# 1-Schematic_starcard.net
KiCad netlist of a schematic drawn in EasyEDA
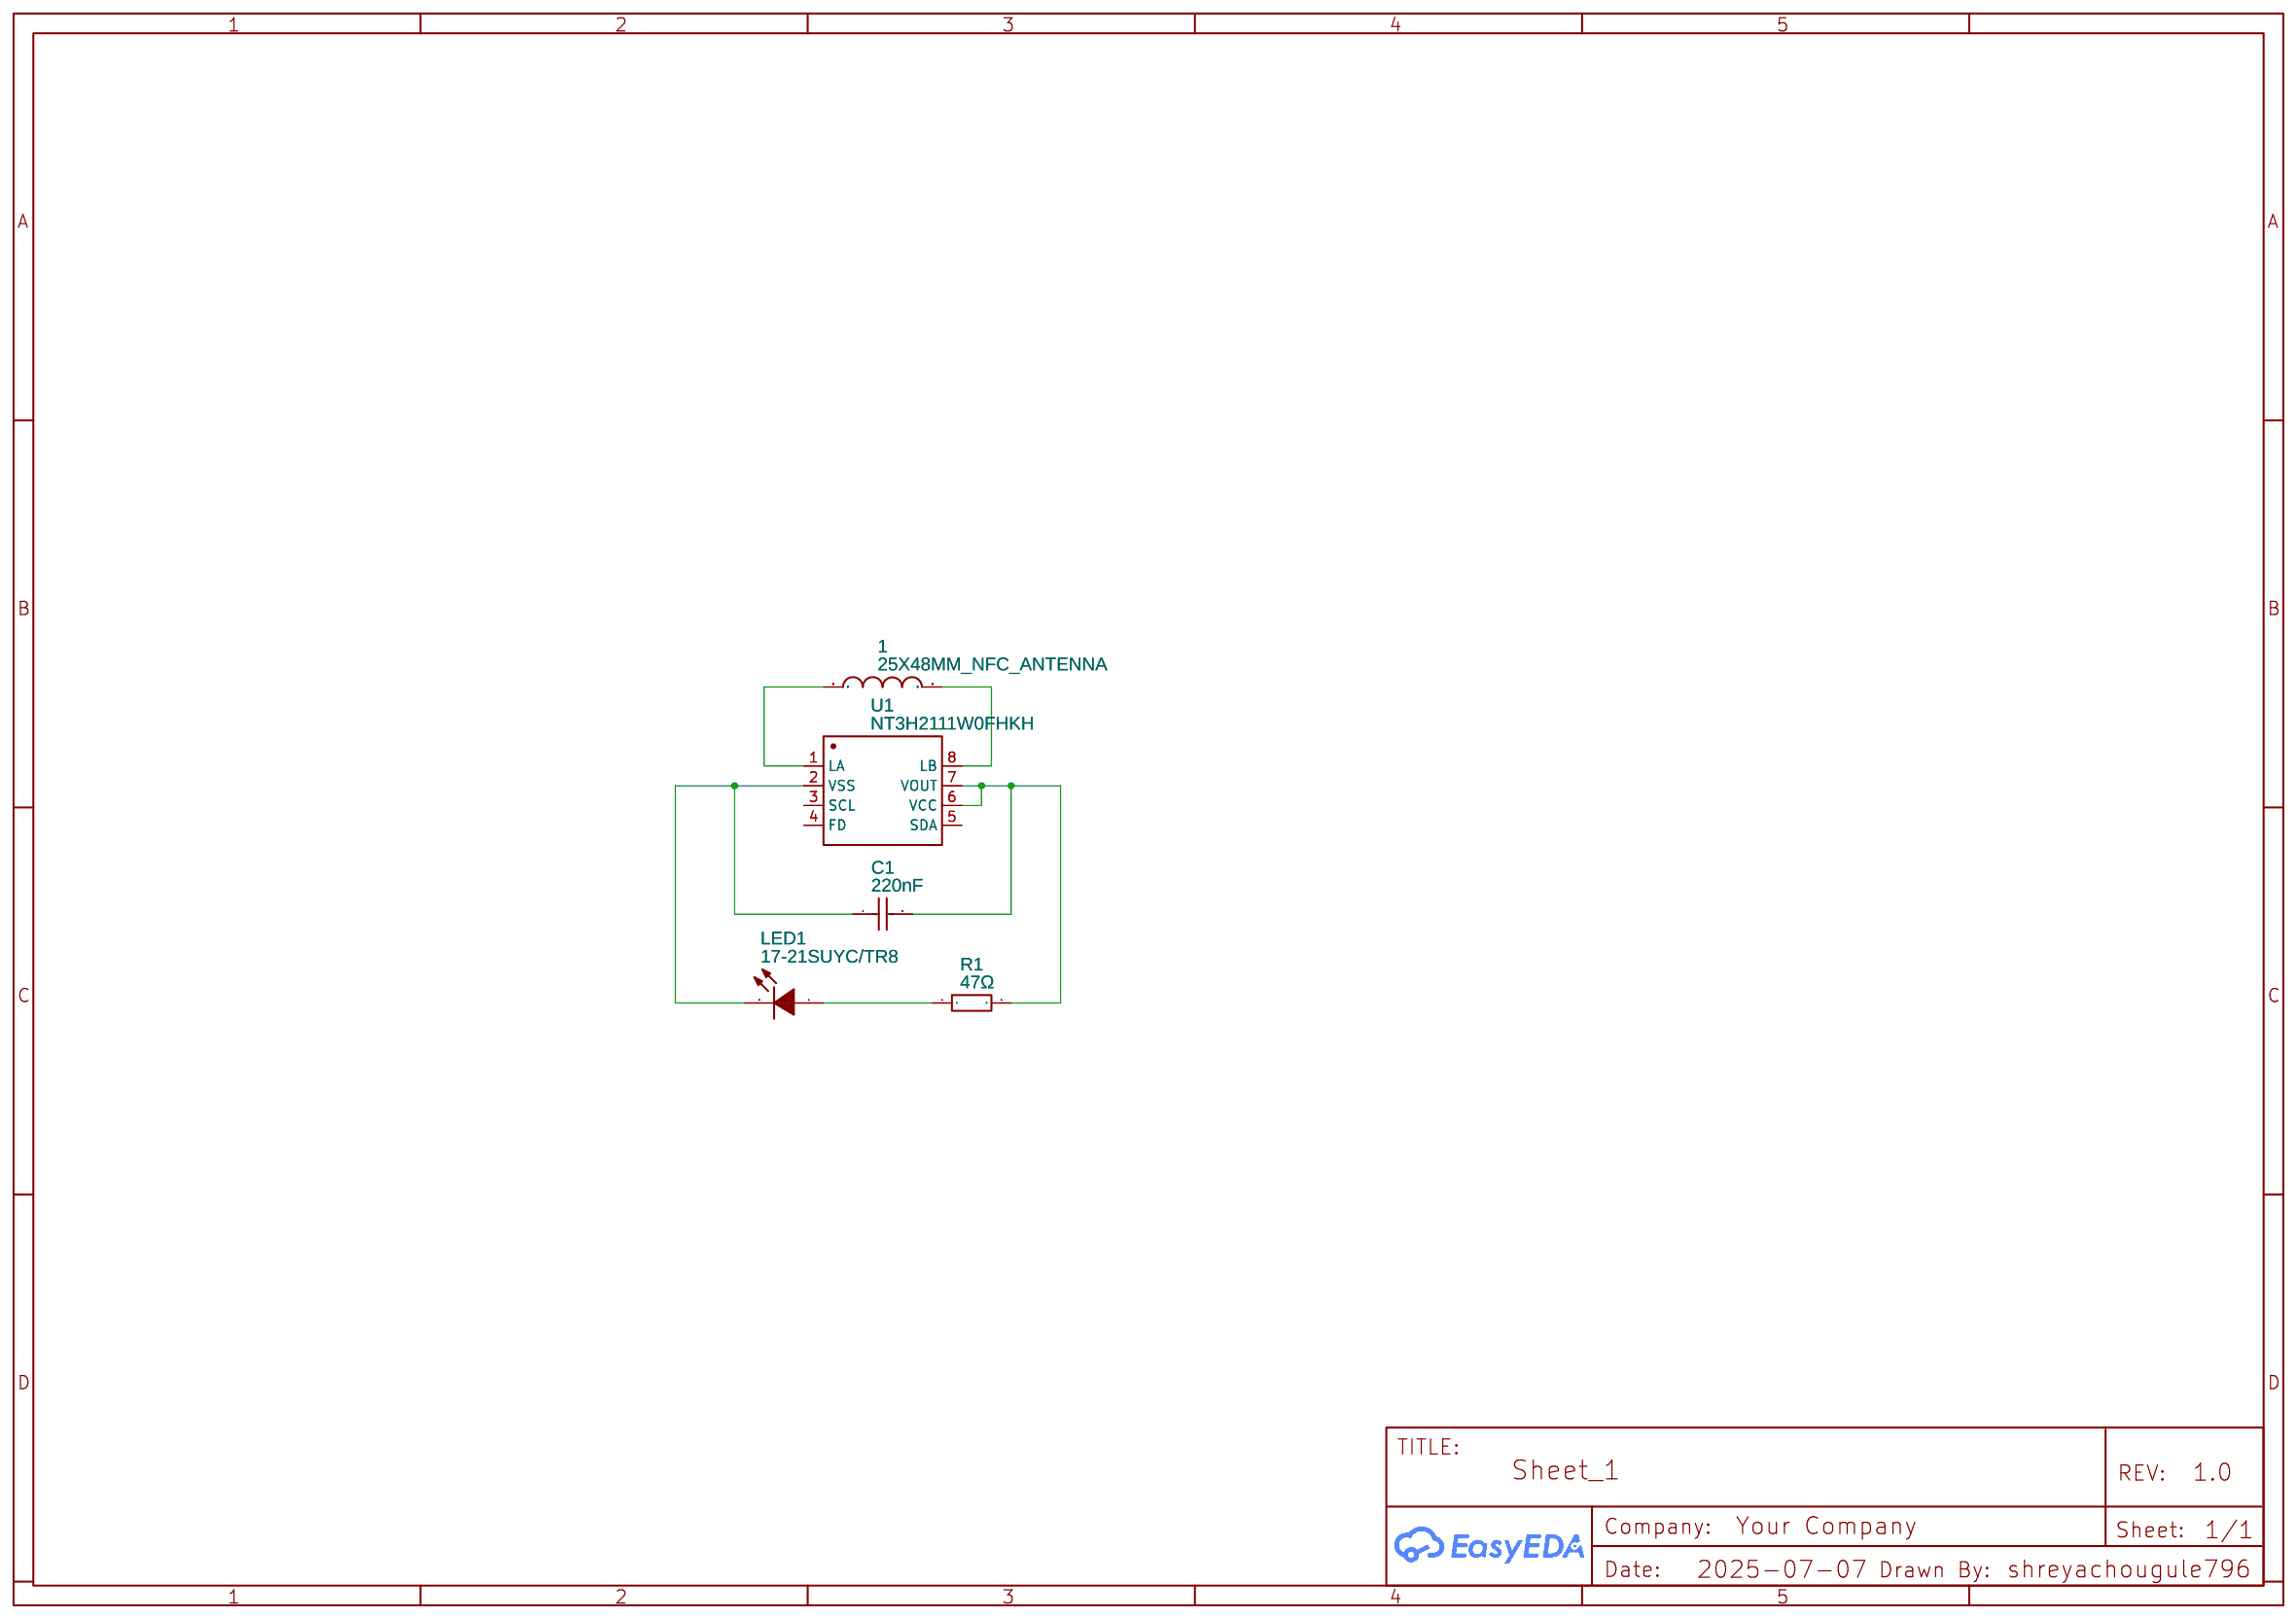
[diagram p0: schematic sheet]

(export (version "E")
  (design (tool "Eeschema 10.0.6"))
  (components
    (comp (ref "1") (value "25X48MM_NFC_ANTENNA") (libsource (lib "") (part "25X48MM_NFC_ANTENNA")))
    (comp (ref "C1")
      (value "220nF")
      (fields
        (field (name "Manufacturer Part") "CL10B224KA8NNNC")
        (field (name "Manufacturer") "SAMSUNG(三星)")
      )
      (libsource (lib "") (part "CL10B224KA8NNNC"))
    )
    (comp (ref "LED1")
      (value "17-21SUYC/TR8")
      (fields (field (name "Manufacturer Part") "KT-0805黄灯") (field (name "Manufacturer") "KENTO"))
      (libsource (lib "") (part "17-21SUYC/TR8"))
    )
    (comp (ref "R1")
      (value "47Ω")
      (fields
        (field (name "Manufacturer Part") "0603WAF470JT5E")
        (field (name "Manufacturer") "UNI-ROYAL(厚声)")
      )
      (libsource (lib "") (part "0603WAF470JT5E"))
    )
    (comp (ref "U1")
      (value "NT3H2111W0FHKH")
      (fields (field (name "Manufacturer") "NXP(恩智浦)"))
      (libsource (lib "") (part "NT3H2111W0FHKH"))
    )
  )
  (nets
    (net (code "1") (name "Net-(LED1-+)") (class "Default")
      (node (ref "LED1") (pin "1") (pinfunction "+_1") (pintype "unspecified"))
      (node (ref "R1") (pin "1") (pinfunction "1_1") (pintype "input"))
    )
    (net (code "2") (name "Net-(LED1--)") (class "Default")
      (node (ref "C1") (pin "1") (pinfunction "1_1") (pintype "input"))
      (node (ref "LED1") (pin "2") (pinfunction "-_2") (pintype "unspecified"))
      (node (ref "U1") (pin "2") (pinfunction "VSS_2") (pintype "unspecified"))
    )
    (net (code "3") (name "Net-(U1-LA)") (class "Default")
      (node (ref "1") (pin "P$1") (pinfunction "P$1_P$1") (pintype "bidirectional"))
      (node (ref "U1") (pin "1") (pinfunction "LA_1") (pintype "unspecified"))
    )
    (net (code "4") (name "Net-(U1-LB)") (class "Default")
      (node (ref "1") (pin "P$2") (pinfunction "P$2_P$2") (pintype "bidirectional"))
      (node (ref "U1") (pin "8") (pinfunction "LB_8") (pintype "unspecified"))
    )
    (net (code "5") (name "Net-(U1-VCC)") (class "Default")
      (node (ref "C1") (pin "2") (pinfunction "2_2") (pintype "input"))
      (node (ref "R1") (pin "2") (pinfunction "2_2") (pintype "input"))
      (node (ref "U1") (pin "6") (pinfunction "VCC_6") (pintype "unspecified"))
      (node (ref "U1") (pin "7") (pinfunction "VOUT_7") (pintype "unspecified"))
    )
    (net (code "6") (name "unconnected-(U1-FD-Pad4)") (class "Default")
      (node (ref "U1") (pin "4") (pinfunction "FD_4") (pintype "unspecified"))
    )
    (net (code "7") (name "unconnected-(U1-SCL-Pad3)") (class "Default")
      (node (ref "U1") (pin "3") (pinfunction "SCL_3") (pintype "unspecified"))
    )
    (net (code "8") (name "unconnected-(U1-SDA-Pad5)") (class "Default")
      (node (ref "U1") (pin "5") (pinfunction "SDA_5") (pintype "unspecified"))
    )
  )
)
